# scoutmakes_robotkit.net
KiCad netlist of a schematic drawn in EAGLE
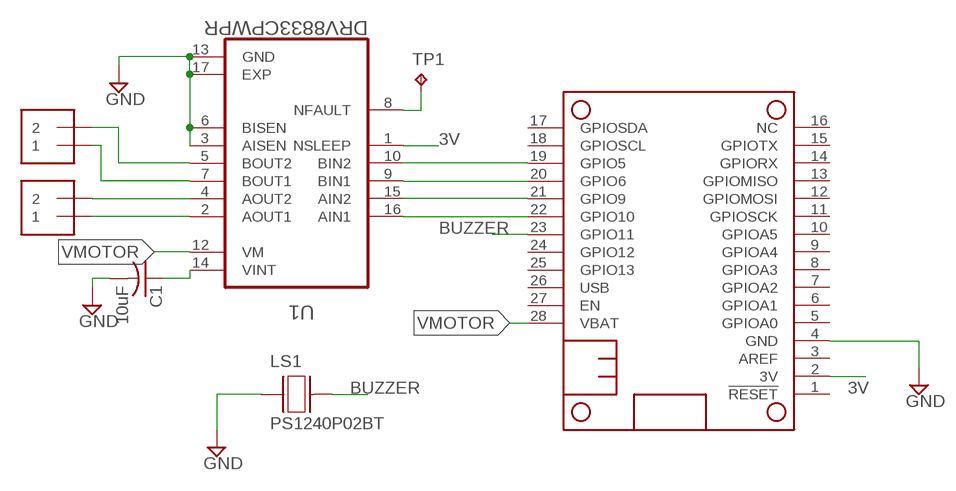
[diagram p0: schematic, sheet 1]

(export (version "E")
  (design (tool "Eeschema 10.0.6"))
  (components
    (comp (ref "C1")
      (value "10uF")
      (footprint "eagle-import:C0805")
      (libsource (lib "eagle-import") (part "C-USC0805"))
    )
    (comp (ref "J1")
      (value "1X2-3.5MM")
      (footprint "eagle-import:1X2-3.5MM")
      (libsource (lib "eagle-import") (part "1X2-3.5MM"))
    )
    (comp (ref "J2")
      (value "1X2-3.5MM")
      (footprint "eagle-import:1X2-3.5MM")
      (libsource (lib "eagle-import") (part "1X2-3.5MM"))
    )
    (comp (ref "LS1")
      (value "PS1240P02BT")
      (footprint "eagle-import:XDCR_PS1240P02BT")
      (fields (field (name "MF") "TDK"))
      (libsource (lib "eagle-import") (part "PS1240P02BT"))
    )
    (comp (ref "MS2")
      (value "FEATHERWING_NODIM")
      (footprint "eagle-import:FEATHERWING_DIM")
      (libsource (lib "eagle-import") (part "FEATHERWING_NODIM"))
    )
    (comp (ref "TP1")
      (value "TPTP09R")
      (footprint "eagle-import:TP09R")
      (libsource (lib "eagle-import") (part "TPTP09R"))
    )
    (comp (ref "U1")
      (value "DRV8833CPWPR")
      (footprint "eagle-import:SOP65P640X120-17N")
      (fields (field (name "MF") "Texas Instruments"))
      (libsource (lib "eagle-import") (part "DRV8833CPWPR"))
    )
  )
  (nets
    (net (code "1") (name "/3V") (class "Default")
      (node (ref "MS2") (pin "2") (pinfunction "3V_2") (pintype "power_in"))
      (node (ref "U1") (pin "1") (pinfunction "NSLEEP_1") (pintype "input"))
    )
    (net (code "2") (name "/BUZZER") (class "Default")
      (node (ref "LS1") (pin "2") (pinfunction "2_2") (pintype "passive"))
      (node (ref "MS2") (pin "23") (pinfunction "GPIO11_23") (pintype "bidirectional"))
    )
    (net (code "3") (name "/USB") (class "Default")
      (node (ref "MS2") (pin "26") (pinfunction "USB_26") (pintype "power_in"))
    )
    (net (code "4") (name "GND") (class "Default")
      (node (ref "C1") (pin "2") (pinfunction "2_2") (pintype "passive"))
      (node (ref "LS1") (pin "1") (pinfunction "1_1") (pintype "passive"))
      (node (ref "MS2") (pin "4") (pinfunction "GND_4") (pintype "power_in"))
      (node (ref "U1") (pin "13") (pinfunction "GND_13") (pintype "power_in"))
      (node (ref "U1") (pin "17") (pinfunction "EXP_17") (pintype "power_in"))
      (node (ref "U1") (pin "3") (pinfunction "AISEN_3") (pintype "output"))
      (node (ref "U1") (pin "6") (pinfunction "BISEN_6") (pintype "output"))
    )
    (net (code "5") (name "Net-(MS2-GPIO5)") (class "Default")
      (node (ref "MS2") (pin "19") (pinfunction "GPIO5_19") (pintype "bidirectional"))
      (node (ref "U1") (pin "10") (pinfunction "BIN2_10") (pintype "input"))
    )
    (net (code "6") (name "Net-(MS2-GPIO6)") (class "Default")
      (node (ref "MS2") (pin "20") (pinfunction "GPIO6_20") (pintype "bidirectional"))
      (node (ref "U1") (pin "9") (pinfunction "BIN1_9") (pintype "input"))
    )
    (net (code "7") (name "Net-(MS2-GPIO9)") (class "Default")
      (node (ref "MS2") (pin "21") (pinfunction "GPIO9_21") (pintype "bidirectional"))
      (node (ref "U1") (pin "15") (pinfunction "AIN2_15") (pintype "input"))
    )
    (net (code "8") (name "Net-(MS2-GPIO10)") (class "Default")
      (node (ref "MS2") (pin "22") (pinfunction "GPIO10_22") (pintype "bidirectional"))
      (node (ref "U1") (pin "16") (pinfunction "AIN1_16") (pintype "input"))
    )
    (net (code "9") (name "Net-(U1-AOUT1)") (class "Default")
      (node (ref "J2") (pin "1") (pinfunction "1_1") (pintype "passive"))
      (node (ref "U1") (pin "2") (pinfunction "AOUT1_2") (pintype "output"))
    )
    (net (code "10") (name "Net-(U1-AOUT2)") (class "Default")
      (node (ref "J2") (pin "2") (pinfunction "2_2") (pintype "passive"))
      (node (ref "U1") (pin "4") (pinfunction "AOUT2_4") (pintype "output"))
    )
    (net (code "11") (name "Net-(U1-BOUT1)") (class "Default")
      (node (ref "J1") (pin "1") (pinfunction "1_1") (pintype "passive"))
      (node (ref "U1") (pin "7") (pinfunction "BOUT1_7") (pintype "output"))
    )
    (net (code "12") (name "Net-(U1-BOUT2)") (class "Default")
      (node (ref "J1") (pin "2") (pinfunction "2_2") (pintype "passive"))
      (node (ref "U1") (pin "5") (pinfunction "BOUT2_5") (pintype "output"))
    )
    (net (code "13") (name "Net-(U1-NFAULT)") (class "Default")
      (node (ref "TP1") (pin "TP") (pinfunction "TP_TP") (pintype "input"))
      (node (ref "U1") (pin "8") (pinfunction "NFAULT_8") (pintype "passive"))
    )
    (net (code "14") (name "Net-(U1-VINT)") (class "Default")
      (node (ref "C1") (pin "1") (pinfunction "1_1") (pintype "passive"))
      (node (ref "U1") (pin "14") (pinfunction "VINT_14") (pintype "power_in"))
    )
    (net (code "15") (name "VMOTOR") (class "Default")
      (node (ref "MS2") (pin "28") (pinfunction "VBAT_28") (pintype "power_in"))
      (node (ref "U1") (pin "12") (pinfunction "VM_12") (pintype "power_in"))
    )
    (net (code "16") (name "unconnected-(MS2-AREF-Pad3)") (class "Default")
      (node (ref "MS2") (pin "3") (pinfunction "AREF_3") (pintype "passive"))
    )
    (net (code "17") (name "unconnected-(MS2-EN-Pad27)") (class "Default")
      (node (ref "MS2") (pin "27") (pinfunction "EN_27") (pintype "passive"))
    )
    (net (code "18") (name "unconnected-(MS2-GPIO12-Pad24)") (class "Default")
      (node (ref "MS2") (pin "24") (pinfunction "GPIO12_24") (pintype "bidirectional"))
    )
    (net (code "19") (name "unconnected-(MS2-GPIO13-Pad25)") (class "Default")
      (node (ref "MS2") (pin "25") (pinfunction "GPIO13_25") (pintype "bidirectional"))
    )
    (net (code "20") (name "unconnected-(MS2-GPIOA0-Pad5)") (class "Default")
      (node (ref "MS2") (pin "5") (pinfunction "GPIOA0_5") (pintype "bidirectional"))
    )
    (net (code "21") (name "unconnected-(MS2-GPIOA1-Pad6)") (class "Default")
      (node (ref "MS2") (pin "6") (pinfunction "GPIOA1_6") (pintype "bidirectional"))
    )
    (net (code "22") (name "unconnected-(MS2-GPIOA2-Pad7)") (class "Default")
      (node (ref "MS2") (pin "7") (pinfunction "GPIOA2_7") (pintype "bidirectional"))
    )
    (net (code "23") (name "unconnected-(MS2-GPIOA3-Pad8)") (class "Default")
      (node (ref "MS2") (pin "8") (pinfunction "GPIOA3_8") (pintype "bidirectional"))
    )
    (net (code "24") (name "unconnected-(MS2-GPIOA4-Pad9)") (class "Default")
      (node (ref "MS2") (pin "9") (pinfunction "GPIOA4_9") (pintype "bidirectional"))
    )
    (net (code "25") (name "unconnected-(MS2-GPIOA5-Pad10)") (class "Default")
      (node (ref "MS2") (pin "10") (pinfunction "GPIOA5_10") (pintype "bidirectional"))
    )
    (net (code "26") (name "unconnected-(MS2-GPIOMISO-Pad13)") (class "Default")
      (node (ref "MS2") (pin "13") (pinfunction "GPIOMISO_13") (pintype "bidirectional"))
    )
    (net (code "27") (name "unconnected-(MS2-GPIOMOSI-Pad12)") (class "Default")
      (node (ref "MS2") (pin "12") (pinfunction "GPIOMOSI_12") (pintype "bidirectional"))
    )
    (net (code "28") (name "unconnected-(MS2-GPIORX-Pad14)") (class "Default")
      (node (ref "MS2") (pin "14") (pinfunction "GPIORX_14") (pintype "bidirectional"))
    )
    (net (code "29") (name "unconnected-(MS2-GPIOSCK-Pad11)") (class "Default")
      (node (ref "MS2") (pin "11") (pinfunction "GPIOSCK_11") (pintype "bidirectional"))
    )
    (net (code "30") (name "unconnected-(MS2-GPIOSCL-Pad18)") (class "Default")
      (node (ref "MS2") (pin "18") (pinfunction "GPIOSCL_18") (pintype "bidirectional"))
    )
    (net (code "31") (name "unconnected-(MS2-GPIOSDA-Pad17)") (class "Default")
      (node (ref "MS2") (pin "17") (pinfunction "GPIOSDA_17") (pintype "bidirectional"))
    )
    (net (code "32") (name "unconnected-(MS2-GPIOTX-Pad15)") (class "Default")
      (node (ref "MS2") (pin "15") (pinfunction "GPIOTX_15") (pintype "bidirectional"))
    )
    (net (code "33") (name "unconnected-(MS2-NC-Pad16)") (class "Default")
      (node (ref "MS2") (pin "16") (pinfunction "NC_16") (pintype "passive"))
    )
    (net (code "34") (name "unconnected-(MS2-~{RESET}-Pad1)") (class "Default")
      (node (ref "MS2") (pin "1") (pinfunction "~{RESET}_1") (pintype "input"))
    )
  )
)
